# CO2_Metar_SCH_0.net
KiCad netlist of a schematic drawn in Altium Designer
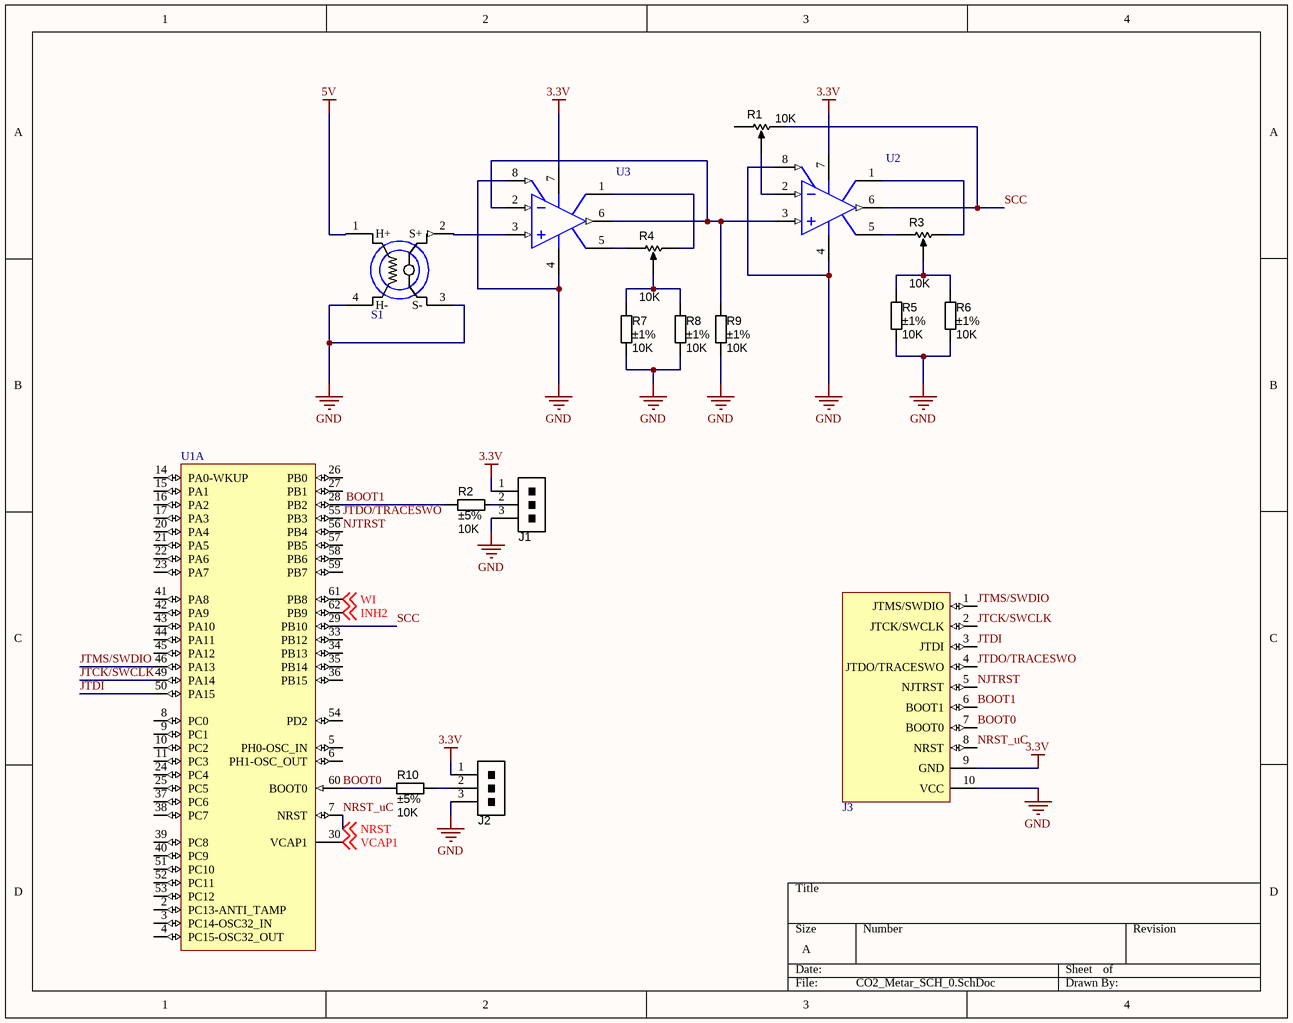
[diagram p0: CO2_Metar_SCH_0.SchDoc]

(export (version "E")
  (design (tool "Eeschema 10.0.6"))
  (components
    (comp (ref "J1")
      (value "*")
      (footprint "1x3POS_HEADER")
      (description "Pin Header, THT, Single-row, 2.54mm pitch")
      (libsource (lib "PBL - Connectors") (part "CONN_HEADER_1x3P_0.100in"))
    )
    (comp (ref "J2")
      (value "*")
      (footprint "1x3POS_HEADER")
      (description "Pin Header, THT, Single-row, 2.54mm pitch")
      (libsource (lib "PBL - Connectors") (part "CONN_HEADER_1x3P_0.100in"))
    )
    (comp (ref "J3")
      (value "*")
      (footprint "SWJ-DP connector")
      (description "10 pin Serial Wire JTAG Debug Port")
      (libsource (lib "co2_meter_integrated_library") (part "SWJ-Debug Port"))
    )
    (comp (ref "R1")
      (value "10K")
      (footprint "TrimPot_SMD_Bourns_3214G")
      (description "Trimmer SMD 10K 250mW 5-turn Side-adjust")
      (fields (field (name "TOLERANCE") "10%") (field (name "Comment") "5 Turn"))
      (libsource (lib "PBL - Resistors") (part "RES_TRIMMER_10K_5T_SMD"))
    )
    (comp (ref "R2")
      (value "10K")
      (footprint "RESC1608X55N")
      (description "Resistor SMD chip 10k Ohm 0.1W 5% 0603")
      (fields (field (name "TOLERANCE") "±5%") (field (name "Comment") "Thick Film"))
      (libsource (lib "PBL - Resistors") (part "RES_10K_0603_5%"))
    )
    (comp (ref "R3")
      (value "10K")
      (footprint "TrimPot_SMD_Bourns_3214G")
      (description "Trimmer SMD 10K 250mW 5-turn Side-adjust")
      (fields (field (name "TOLERANCE") "10%") (field (name "Comment") "5 Turn"))
      (libsource (lib "PBL - Resistors") (part "RES_TRIMMER_10K_5T_SMD"))
    )
    (comp (ref "R4")
      (value "10K")
      (footprint "TrimPot_SMD_Bourns_3214G")
      (description "Trimmer SMD 10K 250mW 5-turn Side-adjust")
      (fields (field (name "TOLERANCE") "10%") (field (name "Comment") "5 Turn"))
      (libsource (lib "PBL - Resistors") (part "RES_TRIMMER_10K_5T_SMD"))
    )
    (comp (ref "R5")
      (value "10K")
      (footprint "RESC1608X55N")
      (description "Resistor SMD chip 10k Ohm 0.1W 1% 0603")
      (fields (field (name "TOLERANCE") "±1%") (field (name "Comment") "Thick Film"))
      (libsource (lib "PBL - Resistors") (part "RES_10K_0603_1%"))
    )
    (comp (ref "R6")
      (value "10K")
      (footprint "RESC1608X55N")
      (description "Resistor SMD chip 10k Ohm 0.1W 1% 0603")
      (fields (field (name "TOLERANCE") "±1%") (field (name "Comment") "Thick Film"))
      (libsource (lib "PBL - Resistors") (part "RES_10K_0603_1%"))
    )
    (comp (ref "R7")
      (value "10K")
      (footprint "RESC1608X55N")
      (description "Resistor SMD chip 10k Ohm 0.1W 1% 0603")
      (fields (field (name "TOLERANCE") "±1%") (field (name "Comment") "Thick Film"))
      (libsource (lib "PBL - Resistors") (part "RES_10K_0603_1%"))
    )
    (comp (ref "R8")
      (value "10K")
      (footprint "RESC1608X55N")
      (description "Resistor SMD chip 10k Ohm 0.1W 1% 0603")
      (fields (field (name "TOLERANCE") "±1%") (field (name "Comment") "Thick Film"))
      (libsource (lib "PBL - Resistors") (part "RES_10K_0603_1%"))
    )
    (comp (ref "R9")
      (value "10K")
      (footprint "RESC1608X55N")
      (description "Resistor SMD chip 10k Ohm 0.1W 1% 0603")
      (fields (field (name "TOLERANCE") "±1%") (field (name "Comment") "Thick Film"))
      (libsource (lib "PBL - Resistors") (part "RES_10K_0603_1%"))
    )
    (comp (ref "R10")
      (value "10K")
      (footprint "RESC1608X55N")
      (description "Resistor SMD chip 10k Ohm 0.1W 5% 0603")
      (fields (field (name "TOLERANCE") "±5%") (field (name "Comment") "Thick Film"))
      (libsource (lib "PBL - Resistors") (part "RES_10K_0603_5%"))
    )
    (comp (ref "S1")
      (value "*")
      (footprint "CO2_SENSOR")
      (description "Solid electrolyte type Carbon Dioxide sensor")
      (libsource (lib "co2_meter_integrated_library") (part "TGS4161"))
    )
    (comp (ref "U1")
      (value "~")
      (footprint "STM-LQFP64_N")
      (fields (field (name "MANUFACTURER") "STMicroelectronics") (field (name "PARTNUMBER") "STM32F401RBT6"))
      (libsource (lib "STMicroelectronics STM32 F4") (part "STM32F401RBT6"))
    )
    (comp (ref "U2")
      (value "~")
      (footprint "D008_L")
      (description "LinCMOS Programmable Low-Power Operational Amplifier")
      (fields (field (name "PUBLISHER") "Altium Limited"))
      (libsource (lib "TI Operational Amplifier (1)") (part "TLC271AID"))
    )
    (comp (ref "U3")
      (value "~")
      (footprint "D008_L")
      (description "LinCMOS Programmable Low-Power Operational Amplifier")
      (fields (field (name "PUBLISHER") "Altium Limited"))
      (libsource (lib "TI Operational Amplifier (1)") (part "TLC271AID"))
    )
  )
  (nets
    (net (code "1") (name "/BOOT0") (class "Default")
      (node (ref "J3") (pin "7") (pinfunction "BOOT0_7") (pintype "bidirectional"))
      (node (ref "R10") (pin "2") (pinfunction "2_2") (pintype "passive"))
      (node (ref "U1") (pin "60") (pinfunction "BOOT0_60") (pintype "input"))
    )
    (net (code "2") (name "/BOOT1") (class "Default")
      (node (ref "J3") (pin "6") (pinfunction "BOOT1_6") (pintype "bidirectional"))
      (node (ref "R2") (pin "2") (pinfunction "2_2") (pintype "passive"))
      (node (ref "U1") (pin "28") (pinfunction "PB2_28") (pintype "bidirectional"))
    )
    (net (code "3") (name "/JTCK{slash}SWCLK") (class "Default")
      (node (ref "J3") (pin "2") (pinfunction "JTCK/SWCLK_2") (pintype "bidirectional"))
      (node (ref "U1") (pin "49") (pinfunction "PA14_49") (pintype "bidirectional"))
    )
    (net (code "4") (name "/JTDI") (class "Default")
      (node (ref "J3") (pin "3") (pinfunction "JTDI_3") (pintype "bidirectional"))
      (node (ref "U1") (pin "50") (pinfunction "PA15_50") (pintype "bidirectional"))
    )
    (net (code "5") (name "/JTDO{slash}TRACESWO") (class "Default")
      (node (ref "J3") (pin "4") (pinfunction "JTDO/TRACESWO_4") (pintype "bidirectional"))
      (node (ref "U1") (pin "55") (pinfunction "PB3_55") (pintype "bidirectional"))
    )
    (net (code "6") (name "/JTMS{slash}SWDIO") (class "Default")
      (node (ref "J3") (pin "1") (pinfunction "JTMS/SWDIO_1") (pintype "bidirectional"))
      (node (ref "U1") (pin "46") (pinfunction "PA13_46") (pintype "bidirectional"))
    )
    (net (code "7") (name "/NJTRST") (class "Default")
      (node (ref "J3") (pin "5") (pinfunction "NJTRST_5") (pintype "bidirectional"))
      (node (ref "U1") (pin "56") (pinfunction "PB4_56") (pintype "bidirectional"))
    )
    (net (code "8") (name "/SCC") (class "Default")
      (node (ref "R1") (pin "3") (pinfunction "CW_3") (pintype "passive"))
      (node (ref "U1") (pin "29") (pinfunction "PB10_29") (pintype "bidirectional"))
      (node (ref "U2") (pin "6") (pinfunction "OUT_6") (pintype "output"))
    )
    (net (code "9") (name "3.3V") (class "Default")
      (node (ref "J1") (pin "1") (pinfunction "1_1") (pintype "passive"))
      (node (ref "J2") (pin "1") (pinfunction "1_1") (pintype "passive"))
      (node (ref "J3") (pin "9") (pinfunction "GND_9") (pintype "power_in"))
      (node (ref "U2") (pin "7") (pinfunction "V+_7") (pintype "power_in"))
      (node (ref "U3") (pin "7") (pinfunction "V+_7") (pintype "power_in"))
    )
    (net (code "10") (name "5V") (class "Default")
      (node (ref "S1") (pin "1") (pinfunction "H+_1") (pintype "power_in"))
    )
    (net (code "11") (name "GND") (class "Default")
      (node (ref "J1") (pin "3") (pinfunction "3_3") (pintype "passive"))
      (node (ref "J2") (pin "3") (pinfunction "3_3") (pintype "passive"))
      (node (ref "J3") (pin "10") (pinfunction "VCC_10") (pintype "power_in"))
      (node (ref "R5") (pin "2") (pinfunction "2_2") (pintype "passive"))
      (node (ref "R6") (pin "2") (pinfunction "2_2") (pintype "passive"))
      (node (ref "R7") (pin "2") (pinfunction "2_2") (pintype "passive"))
      (node (ref "R8") (pin "2") (pinfunction "2_2") (pintype "passive"))
      (node (ref "R9") (pin "2") (pinfunction "2_2") (pintype "passive"))
      (node (ref "S1") (pin "3") (pinfunction "S-_3") (pintype "passive"))
      (node (ref "S1") (pin "4") (pinfunction "H-_4") (pintype "power_in"))
      (node (ref "U2") (pin "4") (pinfunction "V-_4") (pintype "power_in"))
      (node (ref "U2") (pin "8") (pinfunction "BSEL_8") (pintype "input"))
      (node (ref "U3") (pin "4") (pinfunction "V-_4") (pintype "power_in"))
      (node (ref "U3") (pin "8") (pinfunction "BSEL_8") (pintype "input"))
    )
    (net (code "12") (name "INH2") (class "Default")
      (node (ref "U1") (pin "62") (pinfunction "PB9_62") (pintype "bidirectional"))
    )
    (net (code "13") (name "NRST") (class "Default")
      (node (ref "J3") (pin "8") (pinfunction "NRST_8") (pintype "bidirectional"))
      (node (ref "U1") (pin "7") (pinfunction "NRST_7") (pintype "bidirectional"))
    )
    (net (code "14") (name "Net-(J1-Pad2)") (class "Default")
      (node (ref "J1") (pin "2") (pinfunction "2_2") (pintype "passive"))
      (node (ref "R2") (pin "1") (pinfunction "1_1") (pintype "passive"))
    )
    (net (code "15") (name "Net-(J2-Pad2)") (class "Default")
      (node (ref "J2") (pin "2") (pinfunction "2_2") (pintype "passive"))
      (node (ref "R10") (pin "1") (pinfunction "1_1") (pintype "passive"))
    )
    (net (code "16") (name "Net-(R1-WIPER)") (class "Default")
      (node (ref "R1") (pin "2") (pinfunction "WIPER_2") (pintype "passive"))
      (node (ref "U2") (pin "2") (pinfunction "IN-_2") (pintype "input"))
    )
    (net (code "17") (name "Net-(R3-CCW)") (class "Default")
      (node (ref "R3") (pin "1") (pinfunction "CCW_1") (pintype "passive"))
      (node (ref "U2") (pin "5") (pinfunction "OS_N2_5") (pintype "passive"))
    )
    (net (code "18") (name "Net-(R3-CW)") (class "Default")
      (node (ref "R3") (pin "3") (pinfunction "CW_3") (pintype "passive"))
      (node (ref "U2") (pin "1") (pinfunction "OS_N1_1") (pintype "passive"))
    )
    (net (code "19") (name "Net-(R3-WIPER)") (class "Default")
      (node (ref "R3") (pin "2") (pinfunction "WIPER_2") (pintype "passive"))
      (node (ref "R5") (pin "1") (pinfunction "1_1") (pintype "passive"))
      (node (ref "R6") (pin "1") (pinfunction "1_1") (pintype "passive"))
    )
    (net (code "20") (name "Net-(R4-CCW)") (class "Default")
      (node (ref "R4") (pin "1") (pinfunction "CCW_1") (pintype "passive"))
      (node (ref "U3") (pin "5") (pinfunction "OS_N2_5") (pintype "passive"))
    )
    (net (code "21") (name "Net-(R4-CW)") (class "Default")
      (node (ref "R4") (pin "3") (pinfunction "CW_3") (pintype "passive"))
      (node (ref "U3") (pin "1") (pinfunction "OS_N1_1") (pintype "passive"))
    )
    (net (code "22") (name "Net-(R4-WIPER)") (class "Default")
      (node (ref "R4") (pin "2") (pinfunction "WIPER_2") (pintype "passive"))
      (node (ref "R7") (pin "1") (pinfunction "1_1") (pintype "passive"))
      (node (ref "R8") (pin "1") (pinfunction "1_1") (pintype "passive"))
    )
    (net (code "23") (name "Net-(S1-S+)") (class "Default")
      (node (ref "S1") (pin "2") (pinfunction "S+_2") (pintype "output"))
      (node (ref "U3") (pin "3") (pinfunction "IN+_3") (pintype "input"))
    )
    (net (code "24") (name "Net-(U2-IN+)") (class "Default")
      (node (ref "R9") (pin "1") (pinfunction "1_1") (pintype "passive"))
      (node (ref "U2") (pin "3") (pinfunction "IN+_3") (pintype "input"))
      (node (ref "U3") (pin "2") (pinfunction "IN-_2") (pintype "input"))
      (node (ref "U3") (pin "6") (pinfunction "OUT_6") (pintype "output"))
    )
    (net (code "25") (name "VCAP1") (class "Default")
      (node (ref "U1") (pin "30") (pinfunction "VCAP1_30") (pintype "power_in"))
    )
    (net (code "26") (name "WI") (class "Default")
      (node (ref "U1") (pin "61") (pinfunction "PB8_61") (pintype "bidirectional"))
    )
    (net (code "27") (name "unconnected-(R1-CCW-Pad1)") (class "Default")
      (node (ref "R1") (pin "1") (pinfunction "CCW_1") (pintype "passive"))
    )
    (net (code "28") (name "unconnected-(U1A-PA0-WKUP-Pad14)") (class "Default")
      (node (ref "U1") (pin "14") (pinfunction "PA0-WKUP_14") (pintype "bidirectional"))
    )
    (net (code "29") (name "unconnected-(U1A-PA1-Pad15)") (class "Default")
      (node (ref "U1") (pin "15") (pinfunction "PA1_15") (pintype "bidirectional"))
    )
    (net (code "30") (name "unconnected-(U1A-PA2-Pad16)") (class "Default")
      (node (ref "U1") (pin "16") (pinfunction "PA2_16") (pintype "bidirectional"))
    )
    (net (code "31") (name "unconnected-(U1A-PA3-Pad17)") (class "Default")
      (node (ref "U1") (pin "17") (pinfunction "PA3_17") (pintype "bidirectional"))
    )
    (net (code "32") (name "unconnected-(U1A-PA4-Pad20)") (class "Default")
      (node (ref "U1") (pin "20") (pinfunction "PA4_20") (pintype "bidirectional"))
    )
    (net (code "33") (name "unconnected-(U1A-PA5-Pad21)") (class "Default")
      (node (ref "U1") (pin "21") (pinfunction "PA5_21") (pintype "bidirectional"))
    )
    (net (code "34") (name "unconnected-(U1A-PA6-Pad22)") (class "Default")
      (node (ref "U1") (pin "22") (pinfunction "PA6_22") (pintype "bidirectional"))
    )
    (net (code "35") (name "unconnected-(U1A-PA7-Pad23)") (class "Default")
      (node (ref "U1") (pin "23") (pinfunction "PA7_23") (pintype "bidirectional"))
    )
    (net (code "36") (name "unconnected-(U1A-PA8-Pad41)") (class "Default")
      (node (ref "U1") (pin "41") (pinfunction "PA8_41") (pintype "bidirectional"))
    )
    (net (code "37") (name "unconnected-(U1A-PA9-Pad42)") (class "Default")
      (node (ref "U1") (pin "42") (pinfunction "PA9_42") (pintype "bidirectional"))
    )
    (net (code "38") (name "unconnected-(U1A-PA10-Pad43)") (class "Default")
      (node (ref "U1") (pin "43") (pinfunction "PA10_43") (pintype "bidirectional"))
    )
    (net (code "39") (name "unconnected-(U1A-PA11-Pad44)") (class "Default")
      (node (ref "U1") (pin "44") (pinfunction "PA11_44") (pintype "bidirectional"))
    )
    (net (code "40") (name "unconnected-(U1A-PA12-Pad45)") (class "Default")
      (node (ref "U1") (pin "45") (pinfunction "PA12_45") (pintype "bidirectional"))
    )
    (net (code "41") (name "unconnected-(U1A-PB0-Pad26)") (class "Default")
      (node (ref "U1") (pin "26") (pinfunction "PB0_26") (pintype "bidirectional"))
    )
    (net (code "42") (name "unconnected-(U1A-PB1-Pad27)") (class "Default")
      (node (ref "U1") (pin "27") (pinfunction "PB1_27") (pintype "bidirectional"))
    )
    (net (code "43") (name "unconnected-(U1A-PB5-Pad57)") (class "Default")
      (node (ref "U1") (pin "57") (pinfunction "PB5_57") (pintype "bidirectional"))
    )
    (net (code "44") (name "unconnected-(U1A-PB6-Pad58)") (class "Default")
      (node (ref "U1") (pin "58") (pinfunction "PB6_58") (pintype "bidirectional"))
    )
    (net (code "45") (name "unconnected-(U1A-PB7-Pad59)") (class "Default")
      (node (ref "U1") (pin "59") (pinfunction "PB7_59") (pintype "bidirectional"))
    )
    (net (code "46") (name "unconnected-(U1A-PB12-Pad33)") (class "Default")
      (node (ref "U1") (pin "33") (pinfunction "PB12_33") (pintype "bidirectional"))
    )
    (net (code "47") (name "unconnected-(U1A-PB13-Pad34)") (class "Default")
      (node (ref "U1") (pin "34") (pinfunction "PB13_34") (pintype "bidirectional"))
    )
    (net (code "48") (name "unconnected-(U1A-PB14-Pad35)") (class "Default")
      (node (ref "U1") (pin "35") (pinfunction "PB14_35") (pintype "bidirectional"))
    )
    (net (code "49") (name "unconnected-(U1A-PB15-Pad36)") (class "Default")
      (node (ref "U1") (pin "36") (pinfunction "PB15_36") (pintype "bidirectional"))
    )
    (net (code "50") (name "unconnected-(U1A-PC0-Pad8)") (class "Default")
      (node (ref "U1") (pin "8") (pinfunction "PC0_8") (pintype "bidirectional"))
    )
    (net (code "51") (name "unconnected-(U1A-PC1-Pad9)") (class "Default")
      (node (ref "U1") (pin "9") (pinfunction "PC1_9") (pintype "bidirectional"))
    )
    (net (code "52") (name "unconnected-(U1A-PC2-Pad10)") (class "Default")
      (node (ref "U1") (pin "10") (pinfunction "PC2_10") (pintype "bidirectional"))
    )
    (net (code "53") (name "unconnected-(U1A-PC3-Pad11)") (class "Default")
      (node (ref "U1") (pin "11") (pinfunction "PC3_11") (pintype "bidirectional"))
    )
    (net (code "54") (name "unconnected-(U1A-PC4-Pad24)") (class "Default")
      (node (ref "U1") (pin "24") (pinfunction "PC4_24") (pintype "bidirectional"))
    )
    (net (code "55") (name "unconnected-(U1A-PC5-Pad25)") (class "Default")
      (node (ref "U1") (pin "25") (pinfunction "PC5_25") (pintype "bidirectional"))
    )
    (net (code "56") (name "unconnected-(U1A-PC6-Pad37)") (class "Default")
      (node (ref "U1") (pin "37") (pinfunction "PC6_37") (pintype "bidirectional"))
    )
    (net (code "57") (name "unconnected-(U1A-PC7-Pad38)") (class "Default")
      (node (ref "U1") (pin "38") (pinfunction "PC7_38") (pintype "bidirectional"))
    )
    (net (code "58") (name "unconnected-(U1A-PC8-Pad39)") (class "Default")
      (node (ref "U1") (pin "39") (pinfunction "PC8_39") (pintype "bidirectional"))
    )
    (net (code "59") (name "unconnected-(U1A-PC9-Pad40)") (class "Default")
      (node (ref "U1") (pin "40") (pinfunction "PC9_40") (pintype "bidirectional"))
    )
    (net (code "60") (name "unconnected-(U1A-PC10-Pad51)") (class "Default")
      (node (ref "U1") (pin "51") (pinfunction "PC10_51") (pintype "bidirectional"))
    )
    (net (code "61") (name "unconnected-(U1A-PC11-Pad52)") (class "Default")
      (node (ref "U1") (pin "52") (pinfunction "PC11_52") (pintype "bidirectional"))
    )
    (net (code "62") (name "unconnected-(U1A-PC12-Pad53)") (class "Default")
      (node (ref "U1") (pin "53") (pinfunction "PC12_53") (pintype "bidirectional"))
    )
    (net (code "63") (name "unconnected-(U1A-PC13-ANTI_TAMP-Pad2)") (class "Default")
      (node (ref "U1") (pin "2") (pinfunction "PC13-ANTI_TAMP_2") (pintype "bidirectional"))
    )
    (net (code "64") (name "unconnected-(U1A-PC14-OSC32_IN-Pad3)") (class "Default")
      (node (ref "U1") (pin "3") (pinfunction "PC14-OSC32_IN_3") (pintype "bidirectional"))
    )
    (net (code "65") (name "unconnected-(U1A-PC15-OSC32_OUT-Pad4)") (class "Default")
      (node (ref "U1") (pin "4") (pinfunction "PC15-OSC32_OUT_4") (pintype "bidirectional"))
    )
    (net (code "66") (name "unconnected-(U1A-PD2-Pad54)") (class "Default")
      (node (ref "U1") (pin "54") (pinfunction "PD2_54") (pintype "bidirectional"))
    )
    (net (code "67") (name "unconnected-(U1A-PH0-OSC_IN-Pad5)") (class "Default")
      (node (ref "U1") (pin "5") (pinfunction "PH0-OSC_IN_5") (pintype "bidirectional"))
    )
    (net (code "68") (name "unconnected-(U1A-PH1-OSC_OUT-Pad6)") (class "Default")
      (node (ref "U1") (pin "6") (pinfunction "PH1-OSC_OUT_6") (pintype "bidirectional"))
    )
  )
)
